# MPPT_charger.net
KiCad netlist of a schematic drawn in Altium Designer
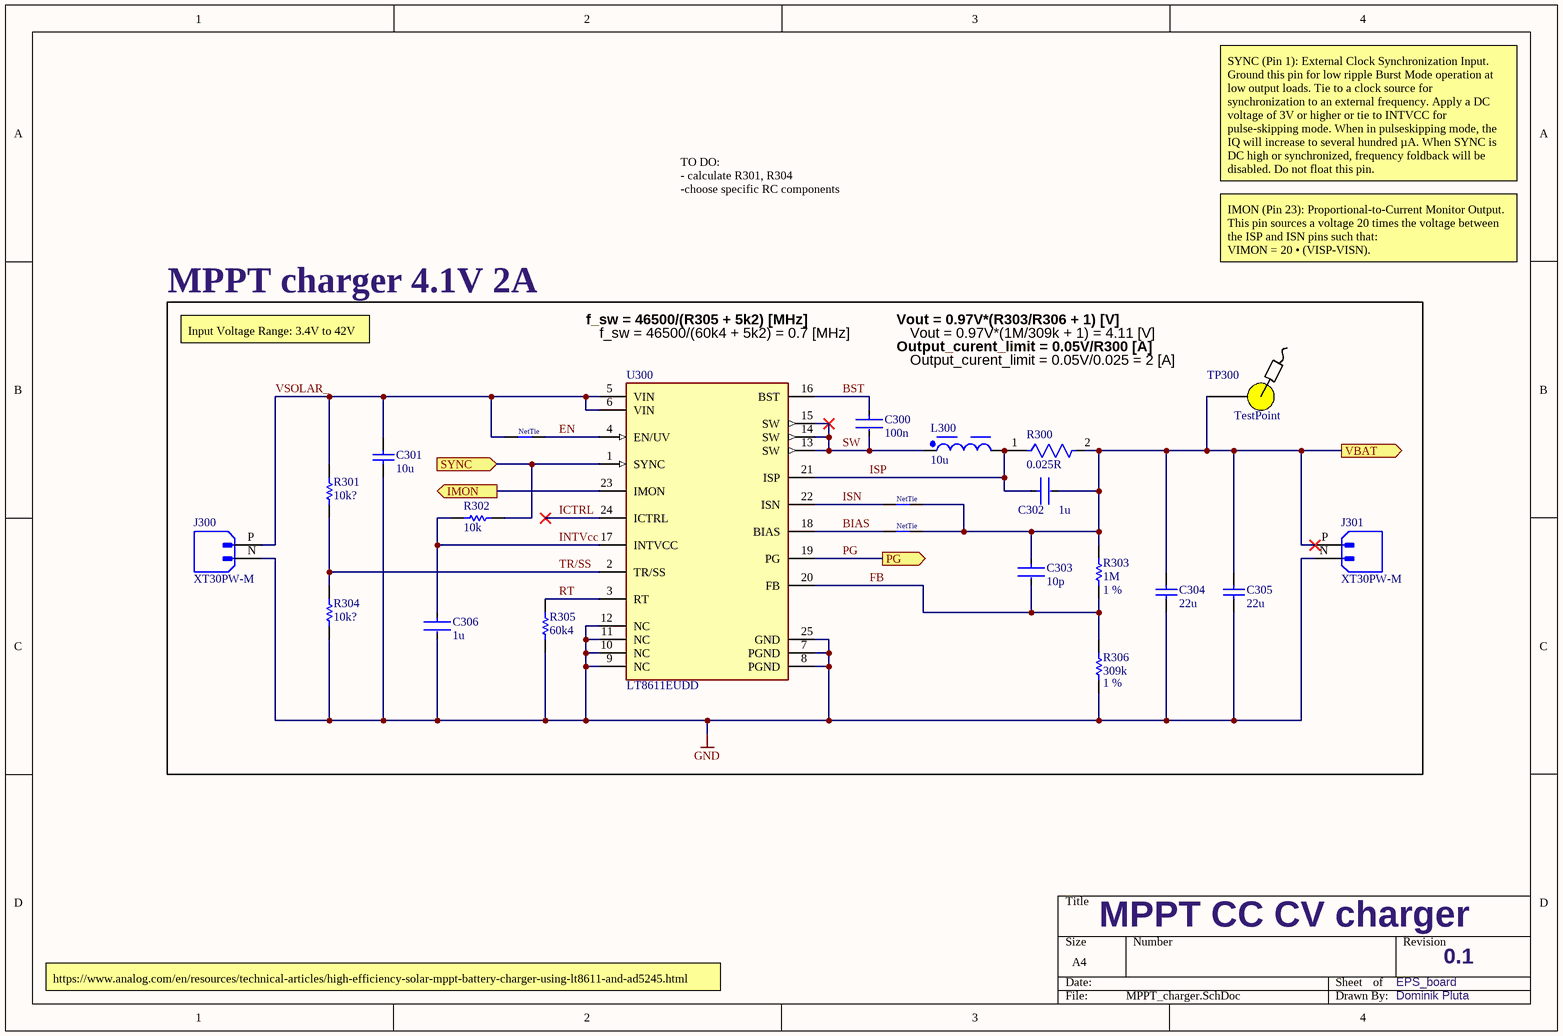
[diagram p0: MPPT_charger.SchDoc]

(export (version "E")
  (design (tool "Eeschema 10.0.6"))
  (components
    (comp (ref "C300")
      (value "100n")
      (footprint "FP-C0603C-CF-MFG")
      (description "CAP CER 50V X7R 0603")
      (fields (field (name "TOLERANCE") "0.1") (field (name "MANUFACTURER") "KEMET"))
      (libsource (lib "Altium Content Vault") (part "b4654b650e69147ec39a6b967a45e02"))
    )
    (comp (ref "C301")
      (value "10u")
      (footprint "KEMT-1206-2_M")
      (description "CAP, Ceramic, 0.1 uF, +/- 10%, 50 V, -55 to 125 degC, 1206 (3216 Metric), RoHS, Tape and Reel")
      (fields (field (name "MANUFACTURER") "Kemet"))
      (libsource (lib "Altium Content Vault") (part "CAP-NP-2"))
    )
    (comp (ref "C302")
      (value "1u")
      (footprint "FP-C0603C-CF-MFG")
      (description "CAP CER 50V X7R 0603")
      (fields (field (name "TOLERANCE") "0.1") (field (name "MANUFACTURER") "KEMET"))
      (libsource (lib "Altium Content Vault") (part "b4654b650e69147ec39a6b967a45e02"))
    )
    (comp (ref "C303")
      (value "10p")
      (footprint "FP-C0603C-CF-MFG")
      (description "CAP CER 50V X7R 0603")
      (fields (field (name "TOLERANCE") "0.1") (field (name "MANUFACTURER") "KEMET"))
      (libsource (lib "Altium Content Vault") (part "b4654b650e69147ec39a6b967a45e02"))
    )
    (comp (ref "C304")
      (value "22u")
      (footprint "KEMT-1206-2_M")
      (description "CAP, Ceramic, 0.1 uF, +/- 10%, 50 V, -55 to 125 degC, 1206 (3216 Metric), RoHS, Tape and Reel")
      (fields (field (name "MANUFACTURER") "Kemet"))
      (libsource (lib "Altium Content Vault") (part "CAP-NP-2"))
    )
    (comp (ref "C305")
      (value "22u")
      (footprint "KEMT-1206-2_M")
      (description "CAP, Ceramic, 0.1 uF, +/- 10%, 50 V, -55 to 125 degC, 1206 (3216 Metric), RoHS, Tape and Reel")
      (fields (field (name "MANUFACTURER") "Kemet"))
      (libsource (lib "Altium Content Vault") (part "CAP-NP-2"))
    )
    (comp (ref "C306")
      (value "1u")
      (footprint "FP-C0603C-CF-MFG")
      (description "CAP CER 50V X7R 0603\r\nLOW ESR!")
      (fields (field (name "TOLERANCE") "0.1") (field (name "MANUFACTURER") "KEMET"))
      (libsource (lib "Altium Content Vault") (part "b4654b650e69147ec39a6b967a45e02"))
    )
    (comp (ref "J300")
      (value "XT30PW-M")
      (footprint "AMASS_XT30PW-M")
      (description "Socket; DC supply; XT30; male; PIN: 2; on PCBs; THT; Colour: yellow")
      (fields (field (name "MF") "AMASS"))
      (libsource (lib "XT30PW-M") (part "XT30PW-M"))
    )
    (comp (ref "J301")
      (value "XT30PW-M")
      (footprint "AMASS_XT30PW-M")
      (description "Socket; DC supply; XT30; male; PIN: 2; on PCBs; THT; Colour: yellow")
      (fields (field (name "MF") "AMASS"))
      (libsource (lib "") (part "XT30PW-M_1"))
    )
    (comp (ref "L300")
      (value "10u")
      (footprint "WE-MAPI_5030")
      (description "74438367100 Power Inductor, 10Uh, Shielded, 4.8A Rohs Compliant: Yes")
      (libsource (lib "Altium Content Vault") (part "Inductor - 2"))
    )
    (comp (ref "NT300")
      (value "NetTie")
      (footprint "NetTie")
      (description "Net tie")
      (libsource (lib "NetTie") (part "NetTie"))
    )
    (comp (ref "NT301")
      (value "NetTie")
      (footprint "NetTie")
      (description "Net tie")
      (libsource (lib "NetTie") (part "NetTie"))
    )
    (comp (ref "NT302")
      (value "NetTie")
      (footprint "NetTie")
      (description "Net tie")
      (libsource (lib "NetTie") (part "NetTie"))
    )
    (comp (ref "R300")
      (value "0.025R")
      (footprint "FP-CR0805-IPC_B")
      (description "Thick Film Chip Resistors 0805 0.025Ω 0.125W 1% 100ppm/°C")
      (fields (field (name "TOLERANCE") "1%"))
      (libsource (lib "Altium Content Vault") (part "1029c3af85768c4190bb7ad29bc67b5"))
    )
    (comp (ref "R301")
      (value "10k?")
      (footprint "RESC0603(1608)_N")
      (description "2K 0.1W 5% 0603 (1608 Metric)  SMD")
      (fields (field (name "TOLERANCE") "5 %") (field (name "POWER") "0.1 W"))
      (libsource (lib "Altium Content Vault") (part "RES"))
    )
    (comp (ref "R302")
      (value "10k")
      (footprint "RESC0603(1608)_N")
      (description "10K 0.1W 5% 0603 (1608 Metric)  SMD")
      (fields (field (name "TOLERANCE") "5 %") (field (name "POWER") "0.1 W"))
      (libsource (lib "Altium Content Vault") (part "RES"))
    )
    (comp (ref "R303")
      (value "1M")
      (footprint "RESC0603(1608)_N")
      (description "1M 0.1W 1% 0603 SMD")
      (fields (field (name "TOLERANCE") "1 %") (field (name "POWER") "0.1 W"))
      (libsource (lib "Altium Content Vault") (part "RES"))
    )
    (comp (ref "R304")
      (value "10k?")
      (footprint "RESC0603(1608)_N")
      (description "2K 0.1W 5% 0603 (1608 Metric)  SMD")
      (fields (field (name "TOLERANCE") "5 %") (field (name "POWER") "0.1 W"))
      (libsource (lib "Altium Content Vault") (part "RES"))
    )
    (comp (ref "R305")
      (value "60k4")
      (footprint "RESC0603(1608)_N")
      (description "2K 0.1W 5% 0603 (1608 Metric)  SMD")
      (fields (field (name "TOLERANCE") "5 %") (field (name "POWER") "0.1 W"))
      (libsource (lib "Altium Content Vault") (part "RES"))
    )
    (comp (ref "R306")
      (value "309k")
      (footprint "RESC0603(1608)_N")
      (description "309k 0.1W 1% 0603 SMD")
      (fields (field (name "TOLERANCE") "1 %") (field (name "POWER") "0.1 W"))
      (libsource (lib "Altium Content Vault") (part "RES"))
    )
    (comp (ref "TP300")
      (value "TestPoint")
      (footprint "Test-point")
      (description "SMD test point")
      (libsource (lib "TestPoint") (part "Test-point"))
    )
    (comp (ref "U300")
      (value "LT8611EUDD")
      (footprint "FP-UDD-24-05-08-1833-IPC_B")
      (description "IC REG BUCK ADJ 2.5A 24QFN")
      (libsource (lib "Altium Content Vault") (part "fa917c90ce6974f84498b26f3756de5"))
    )
  )
  (nets
    (net (code "1") (name "/BIAS") (class "Default")
      (node (ref "NT302") (pin "1") (pinfunction "1_1") (pintype "passive"))
      (node (ref "U300") (pin "18") (pinfunction "BIAS_18") (pintype "passive"))
    )
    (net (code "2") (name "/BST") (class "Default")
      (node (ref "C300") (pin "1") (pinfunction "1_1") (pintype "passive"))
      (node (ref "U300") (pin "16") (pinfunction "BST_16") (pintype "passive"))
    )
    (net (code "3") (name "/EN") (class "Default")
      (node (ref "NT300") (pin "2") (pinfunction "2_2") (pintype "passive"))
      (node (ref "U300") (pin "4") (pinfunction "EN/UV_4") (pintype "input"))
    )
    (net (code "4") (name "/FB") (class "Default")
      (node (ref "C303") (pin "2") (pinfunction "2_2") (pintype "passive"))
      (node (ref "R303") (pin "1") (pinfunction "1_1") (pintype "passive"))
      (node (ref "R306") (pin "2") (pinfunction "2_2") (pintype "passive"))
      (node (ref "U300") (pin "20") (pinfunction "FB_20") (pintype "passive"))
    )
    (net (code "5") (name "/ICTRL") (class "Default")
      (node (ref "U300") (pin "24") (pinfunction "ICTRL_24") (pintype "passive+no_connect"))
    )
    (net (code "6") (name "/IMON") (class "Default")
      (node (ref "U300") (pin "23") (pinfunction "IMON_23") (pintype "passive"))
    )
    (net (code "7") (name "/INTVcc") (class "Default")
      (node (ref "C306") (pin "1") (pinfunction "1_1") (pintype "passive"))
      (node (ref "R302") (pin "2") (pinfunction "2_2") (pintype "passive"))
      (node (ref "U300") (pin "17") (pinfunction "INTVCC_17") (pintype "passive"))
    )
    (net (code "8") (name "/ISN") (class "Default")
      (node (ref "NT301") (pin "1") (pinfunction "1_1") (pintype "passive"))
      (node (ref "U300") (pin "22") (pinfunction "ISN_22") (pintype "passive"))
    )
    (net (code "9") (name "/ISP") (class "Default")
      (node (ref "C302") (pin "1") (pinfunction "1_1") (pintype "passive"))
      (node (ref "L300") (pin "2") (pinfunction "2_2") (pintype "passive"))
      (node (ref "R300") (pin "1") (pinfunction "1_1") (pintype "passive"))
      (node (ref "U300") (pin "21") (pinfunction "ISP_21") (pintype "passive"))
    )
    (net (code "10") (name "/PG") (class "Default")
      (node (ref "U300") (pin "19") (pinfunction "PG_19") (pintype "passive"))
    )
    (net (code "11") (name "/RT") (class "Default")
      (node (ref "R305") (pin "2") (pinfunction "2_2") (pintype "passive"))
      (node (ref "U300") (pin "3") (pinfunction "RT_3") (pintype "passive"))
    )
    (net (code "12") (name "/SW") (class "Default")
      (node (ref "C300") (pin "2") (pinfunction "2_2") (pintype "passive"))
      (node (ref "L300") (pin "1") (pinfunction "1_1") (pintype "passive"))
      (node (ref "U300") (pin "13") (pinfunction "SW_13") (pintype "output"))
      (node (ref "U300") (pin "14") (pinfunction "SW_14") (pintype "output"))
      (node (ref "U300") (pin "15") (pinfunction "SW_15") (pintype "output"))
    )
    (net (code "13") (name "/SYNC") (class "Default")
      (node (ref "R302") (pin "1") (pinfunction "1_1") (pintype "passive"))
      (node (ref "U300") (pin "1") (pinfunction "SYNC_1") (pintype "input"))
    )
    (net (code "14") (name "/TR{slash}SS") (class "Default")
      (node (ref "R301") (pin "1") (pinfunction "1_1") (pintype "passive"))
      (node (ref "R304") (pin "2") (pinfunction "2_2") (pintype "passive"))
      (node (ref "U300") (pin "2") (pinfunction "TR/SS_2") (pintype "passive"))
    )
    (net (code "15") (name "/VBAT") (class "Default")
      (node (ref "C302") (pin "2") (pinfunction "2_2") (pintype "passive"))
      (node (ref "C303") (pin "1") (pinfunction "1_1") (pintype "passive"))
      (node (ref "C304") (pin "2") (pinfunction "2_2") (pintype "passive"))
      (node (ref "C305") (pin "2") (pinfunction "2_2") (pintype "passive"))
      (node (ref "J301") (pin "P") (pinfunction "P_P") (pintype "power_in"))
      (node (ref "NT301") (pin "2") (pinfunction "2_2") (pintype "passive"))
      (node (ref "NT302") (pin "2") (pinfunction "2_2") (pintype "passive"))
      (node (ref "R300") (pin "2") (pinfunction "2_2") (pintype "passive"))
      (node (ref "R303") (pin "2") (pinfunction "2_2") (pintype "passive"))
      (node (ref "TP300") (pin "1") (pintype "passive"))
    )
    (net (code "16") (name "/VSOLAR_") (class "Default")
      (node (ref "C301") (pin "2") (pinfunction "2_2") (pintype "passive"))
      (node (ref "J300") (pin "P") (pinfunction "P_P") (pintype "power_in"))
      (node (ref "NT300") (pin "1") (pinfunction "1_1") (pintype "passive"))
      (node (ref "R301") (pin "2") (pinfunction "2_2") (pintype "passive"))
      (node (ref "U300") (pin "5") (pinfunction "VIN_5") (pintype "power_in"))
      (node (ref "U300") (pin "6") (pinfunction "VIN_6") (pintype "power_in"))
    )
    (net (code "17") (name "GND") (class "Default")
      (node (ref "C301") (pin "1") (pinfunction "1_1") (pintype "passive"))
      (node (ref "C304") (pin "1") (pinfunction "1_1") (pintype "passive"))
      (node (ref "C305") (pin "1") (pinfunction "1_1") (pintype "passive"))
      (node (ref "C306") (pin "2") (pinfunction "2_2") (pintype "passive"))
      (node (ref "J300") (pin "N") (pinfunction "N_N") (pintype "power_in"))
      (node (ref "J301") (pin "N") (pinfunction "N_N") (pintype "power_in"))
      (node (ref "R304") (pin "1") (pinfunction "1_1") (pintype "passive"))
      (node (ref "R305") (pin "1") (pinfunction "1_1") (pintype "passive"))
      (node (ref "R306") (pin "1") (pinfunction "1_1") (pintype "passive"))
      (node (ref "U300") (pin "10") (pinfunction "NC_10") (pintype "passive"))
      (node (ref "U300") (pin "11") (pinfunction "NC_11") (pintype "passive"))
      (node (ref "U300") (pin "12") (pinfunction "NC_12") (pintype "passive"))
      (node (ref "U300") (pin "25") (pinfunction "GND_25") (pintype "power_in"))
      (node (ref "U300") (pin "7") (pinfunction "PGND_7") (pintype "power_in"))
      (node (ref "U300") (pin "8") (pinfunction "PGND_8") (pintype "power_in"))
      (node (ref "U300") (pin "9") (pinfunction "NC_9") (pintype "passive"))
    )
  )
)
